# macropad.net
KiCad netlist of a schematic drawn in EAGLE
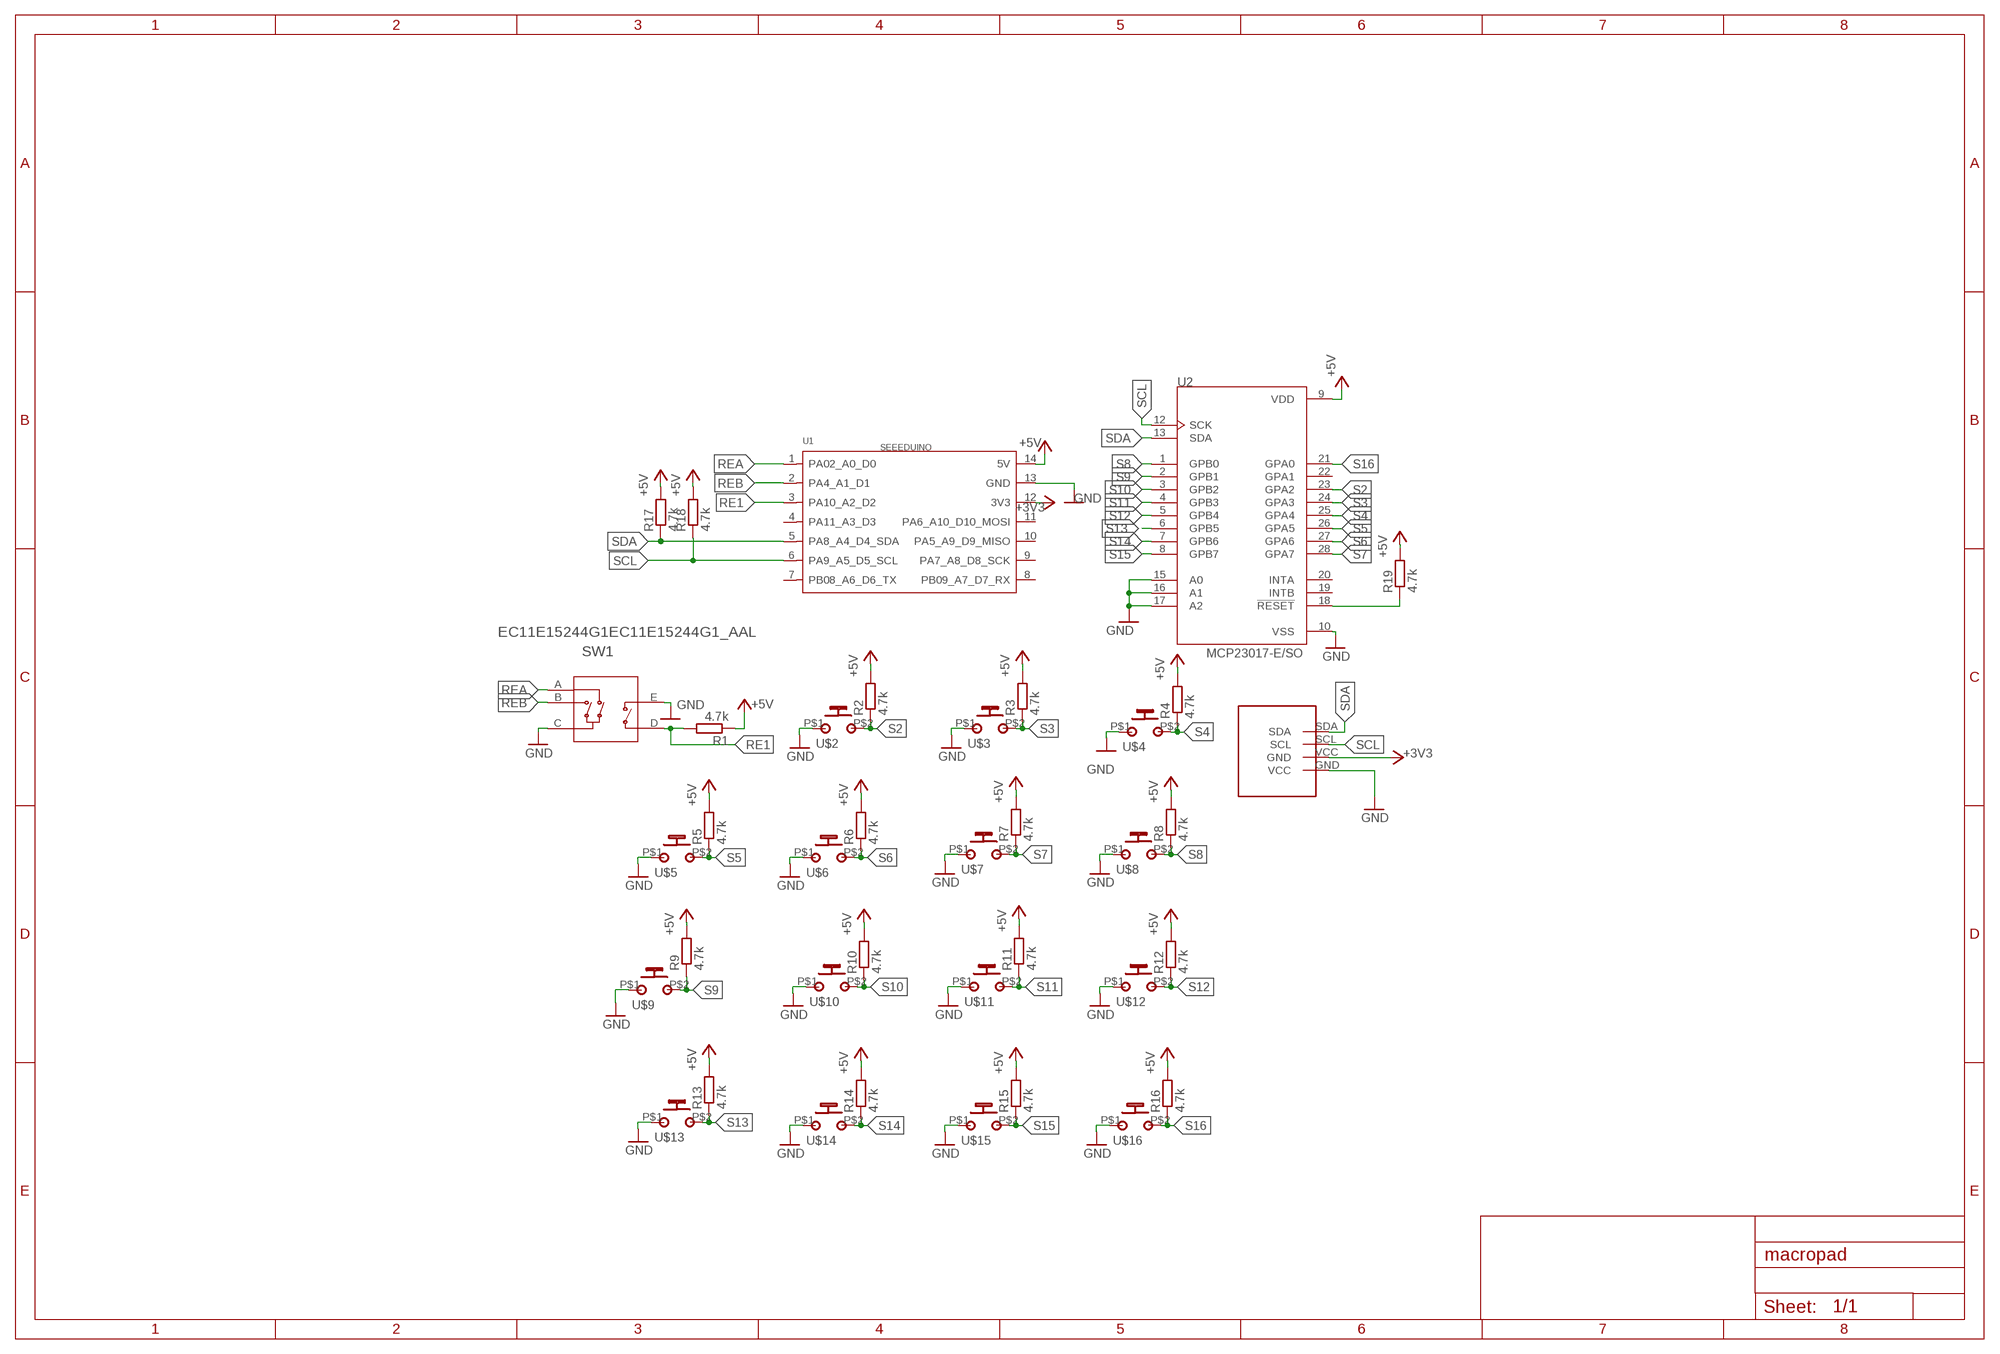
[diagram p0: schematic, sheet 1]

(export (version "E")
  (design (tool "Eeschema 10.0.6"))
  (components
    (comp (ref "DISPLAY")
      (value "OLED_0.96_I2C")
      (footprint "eagle-import:OLED_0.96_I2C")
      (libsource (lib "eagle-import") (part "OLED_0.96_I2C"))
    )
    (comp (ref "R1")
      (value "4.7k")
      (footprint "eagle-import:R0805")
      (libsource (lib "eagle-import") (part "R-EU_R0805"))
    )
    (comp (ref "R2")
      (value "4.7k")
      (footprint "eagle-import:R0805")
      (libsource (lib "eagle-import") (part "R-EU_R0805"))
    )
    (comp (ref "R3")
      (value "4.7k")
      (footprint "eagle-import:R0805")
      (libsource (lib "eagle-import") (part "R-EU_R0805"))
    )
    (comp (ref "R4")
      (value "4.7k")
      (footprint "eagle-import:R0805")
      (libsource (lib "eagle-import") (part "R-EU_R0805"))
    )
    (comp (ref "R5")
      (value "4.7k")
      (footprint "eagle-import:R0805")
      (libsource (lib "eagle-import") (part "R-EU_R0805"))
    )
    (comp (ref "R6")
      (value "4.7k")
      (footprint "eagle-import:R0805")
      (libsource (lib "eagle-import") (part "R-EU_R0805"))
    )
    (comp (ref "R7")
      (value "4.7k")
      (footprint "eagle-import:R0805")
      (libsource (lib "eagle-import") (part "R-EU_R0805"))
    )
    (comp (ref "R8")
      (value "4.7k")
      (footprint "eagle-import:R0805")
      (libsource (lib "eagle-import") (part "R-EU_R0805"))
    )
    (comp (ref "R9")
      (value "4.7k")
      (footprint "eagle-import:R0805")
      (libsource (lib "eagle-import") (part "R-EU_R0805"))
    )
    (comp (ref "R10")
      (value "4.7k")
      (footprint "eagle-import:R0805")
      (libsource (lib "eagle-import") (part "R-EU_R0805"))
    )
    (comp (ref "R11")
      (value "4.7k")
      (footprint "eagle-import:R0805")
      (libsource (lib "eagle-import") (part "R-EU_R0805"))
    )
    (comp (ref "R12")
      (value "4.7k")
      (footprint "eagle-import:R0805")
      (libsource (lib "eagle-import") (part "R-EU_R0805"))
    )
    (comp (ref "R13")
      (value "4.7k")
      (footprint "eagle-import:R0805")
      (libsource (lib "eagle-import") (part "R-EU_R0805"))
    )
    (comp (ref "R14")
      (value "4.7k")
      (footprint "eagle-import:R0805")
      (libsource (lib "eagle-import") (part "R-EU_R0805"))
    )
    (comp (ref "R15")
      (value "4.7k")
      (footprint "eagle-import:R0805")
      (libsource (lib "eagle-import") (part "R-EU_R0805"))
    )
    (comp (ref "R16")
      (value "4.7k")
      (footprint "eagle-import:R0805")
      (libsource (lib "eagle-import") (part "R-EU_R0805"))
    )
    (comp (ref "R17")
      (value "4.7k")
      (footprint "eagle-import:R0805")
      (libsource (lib "eagle-import") (part "R-EU_R0805"))
    )
    (comp (ref "R18")
      (value "4.7k")
      (footprint "eagle-import:R0805")
      (libsource (lib "eagle-import") (part "R-EU_R0805"))
    )
    (comp (ref "R19")
      (value "4.7k")
      (footprint "eagle-import:R0805")
      (libsource (lib "eagle-import") (part "R-EU_R0805"))
    )
    (comp (ref "SW1")
      (value "EC11E15244G1EC11E15244G1_AAL")
      (footprint "eagle-import:EC11E15244G1_AAL")
      (fields
        (field (name "MANUFACTURER_PART_NUMBER") "EC11E15244G1")
        (field (name "COPYRIGHT") "Copyright (C) 2023 Ultra Librarian. All rights reserved.")
      )
      (libsource (lib "eagle-import") (part "EC11E15244G1EC11E15244G1_AAL"))
    )
    (comp (ref "U$2")
      (value "MX1A-11NN")
      (footprint "eagle-import:CHERRY_MX1A-11NN_SWITCH")
      (fields (field (name "MF") "Cherry") (field (name "MP") "MX1A11NN"))
      (libsource (lib "eagle-import") (part "MX1A-11NN"))
    )
    (comp (ref "U$3")
      (value "MX1A-11NN")
      (footprint "eagle-import:CHERRY_MX1A-11NN_SWITCH")
      (fields (field (name "MF") "Cherry") (field (name "MP") "MX1A11NN"))
      (libsource (lib "eagle-import") (part "MX1A-11NN"))
    )
    (comp (ref "U$4")
      (value "MX1A-11NN")
      (footprint "eagle-import:CHERRY_MX1A-11NN_SWITCH")
      (fields (field (name "MF") "Cherry") (field (name "MP") "MX1A11NN"))
      (libsource (lib "eagle-import") (part "MX1A-11NN"))
    )
    (comp (ref "U$5")
      (value "MX1A-11NN")
      (footprint "eagle-import:CHERRY_MX1A-11NN_SWITCH")
      (fields (field (name "MF") "Cherry") (field (name "MP") "MX1A11NN"))
      (libsource (lib "eagle-import") (part "MX1A-11NN"))
    )
    (comp (ref "U$6")
      (value "MX1A-11NN")
      (footprint "eagle-import:CHERRY_MX1A-11NN_SWITCH")
      (fields (field (name "MF") "Cherry") (field (name "MP") "MX1A11NN"))
      (libsource (lib "eagle-import") (part "MX1A-11NN"))
    )
    (comp (ref "U$7")
      (value "MX1A-11NN")
      (footprint "eagle-import:CHERRY_MX1A-11NN_SWITCH")
      (fields (field (name "MF") "Cherry") (field (name "MP") "MX1A11NN"))
      (libsource (lib "eagle-import") (part "MX1A-11NN"))
    )
    (comp (ref "U$8")
      (value "MX1A-11NN")
      (footprint "eagle-import:CHERRY_MX1A-11NN_SWITCH")
      (fields (field (name "MF") "Cherry") (field (name "MP") "MX1A11NN"))
      (libsource (lib "eagle-import") (part "MX1A-11NN"))
    )
    (comp (ref "U$9")
      (value "MX1A-11NN")
      (footprint "eagle-import:CHERRY_MX1A-11NN_SWITCH")
      (fields (field (name "MF") "Cherry") (field (name "MP") "MX1A11NN"))
      (libsource (lib "eagle-import") (part "MX1A-11NN"))
    )
    (comp (ref "U$10")
      (value "MX1A-11NN")
      (footprint "eagle-import:CHERRY_MX1A-11NN_SWITCH")
      (fields (field (name "MF") "Cherry") (field (name "MP") "MX1A11NN"))
      (libsource (lib "eagle-import") (part "MX1A-11NN"))
    )
    (comp (ref "U$11")
      (value "MX1A-11NN")
      (footprint "eagle-import:CHERRY_MX1A-11NN_SWITCH")
      (fields (field (name "MF") "Cherry") (field (name "MP") "MX1A11NN"))
      (libsource (lib "eagle-import") (part "MX1A-11NN"))
    )
    (comp (ref "U$12")
      (value "MX1A-11NN")
      (footprint "eagle-import:CHERRY_MX1A-11NN_SWITCH")
      (fields (field (name "MF") "Cherry") (field (name "MP") "MX1A11NN"))
      (libsource (lib "eagle-import") (part "MX1A-11NN"))
    )
    (comp (ref "U$13")
      (value "MX1A-11NN")
      (footprint "eagle-import:CHERRY_MX1A-11NN_SWITCH")
      (fields (field (name "MF") "Cherry") (field (name "MP") "MX1A11NN"))
      (libsource (lib "eagle-import") (part "MX1A-11NN"))
    )
    (comp (ref "U$14")
      (value "MX1A-11NN")
      (footprint "eagle-import:CHERRY_MX1A-11NN_SWITCH")
      (fields (field (name "MF") "Cherry") (field (name "MP") "MX1A11NN"))
      (libsource (lib "eagle-import") (part "MX1A-11NN"))
    )
    (comp (ref "U$15")
      (value "MX1A-11NN")
      (footprint "eagle-import:CHERRY_MX1A-11NN_SWITCH")
      (fields (field (name "MF") "Cherry") (field (name "MP") "MX1A11NN"))
      (libsource (lib "eagle-import") (part "MX1A-11NN"))
    )
    (comp (ref "U$16")
      (value "MX1A-11NN")
      (footprint "eagle-import:CHERRY_MX1A-11NN_SWITCH")
      (fields (field (name "MF") "Cherry") (field (name "MP") "MX1A11NN"))
      (libsource (lib "eagle-import") (part "MX1A-11NN"))
    )
    (comp (ref "U1")
      (value "SEEEDUINO")
      (footprint "eagle-import:MOUDLE14P-2.54-21X17.8MM")
      (libsource (lib "eagle-import") (part "MOUDLE-SEEEDUINO-XIAO"))
    )
    (comp (ref "U2")
      (value "MCP23017-E/SO")
      (footprint "eagle-import:SOIC127P1030X265-28N")
      (fields (field (name "MF") "Microchip"))
      (libsource (lib "eagle-import") (part "MCP23017-E/SO"))
    )
  )
  (nets
    (net (code "1") (name "+3V3") (class "Default")
      (node (ref "DISPLAY") (pin "VCC") (pinfunction "GND_VCC") (pintype "bidirectional"))
      (node (ref "U1") (pin "12") (pinfunction "3V3_12") (pintype "bidirectional"))
    )
    (net (code "2") (name "+5V") (class "Default")
      (node (ref "R1") (pin "1") (pinfunction "1_1") (pintype "passive"))
      (node (ref "R10") (pin "2") (pinfunction "2_2") (pintype "passive"))
      (node (ref "R11") (pin "2") (pinfunction "2_2") (pintype "passive"))
      (node (ref "R12") (pin "2") (pinfunction "2_2") (pintype "passive"))
      (node (ref "R13") (pin "2") (pinfunction "2_2") (pintype "passive"))
      (node (ref "R14") (pin "2") (pinfunction "2_2") (pintype "passive"))
      (node (ref "R15") (pin "2") (pinfunction "2_2") (pintype "passive"))
      (node (ref "R16") (pin "2") (pinfunction "2_2") (pintype "passive"))
      (node (ref "R17") (pin "2") (pinfunction "2_2") (pintype "passive"))
      (node (ref "R18") (pin "2") (pinfunction "2_2") (pintype "passive"))
      (node (ref "R19") (pin "2") (pinfunction "2_2") (pintype "passive"))
      (node (ref "R2") (pin "2") (pinfunction "2_2") (pintype "passive"))
      (node (ref "R3") (pin "2") (pinfunction "2_2") (pintype "passive"))
      (node (ref "R4") (pin "2") (pinfunction "2_2") (pintype "passive"))
      (node (ref "R5") (pin "2") (pinfunction "2_2") (pintype "passive"))
      (node (ref "R6") (pin "2") (pinfunction "2_2") (pintype "passive"))
      (node (ref "R7") (pin "2") (pinfunction "2_2") (pintype "passive"))
      (node (ref "R8") (pin "2") (pinfunction "2_2") (pintype "passive"))
      (node (ref "R9") (pin "2") (pinfunction "2_2") (pintype "passive"))
      (node (ref "U1") (pin "14") (pinfunction "5V_14") (pintype "bidirectional"))
      (node (ref "U2") (pin "9") (pinfunction "VDD_9") (pintype "power_in"))
    )
    (net (code "3") (name "GND") (class "Default")
      (node (ref "DISPLAY") (pin "GND") (pinfunction "VCC_GND") (pintype "bidirectional"))
      (node (ref "SW1") (pin "C") (pinfunction "C_C") (pintype "passive"))
      (node (ref "SW1") (pin "E") (pinfunction "E_E") (pintype "passive"))
      (node (ref "U$10") (pin "P$1") (pinfunction "P_P$1") (pintype "passive"))
      (node (ref "U$11") (pin "P$1") (pinfunction "P_P$1") (pintype "passive"))
      (node (ref "U$12") (pin "P$1") (pinfunction "P_P$1") (pintype "passive"))
      (node (ref "U$13") (pin "P$1") (pinfunction "P_P$1") (pintype "passive"))
      (node (ref "U$14") (pin "P$1") (pinfunction "P_P$1") (pintype "passive"))
      (node (ref "U$15") (pin "P$1") (pinfunction "P_P$1") (pintype "passive"))
      (node (ref "U$16") (pin "P$1") (pinfunction "P_P$1") (pintype "passive"))
      (node (ref "U$2") (pin "P$1") (pinfunction "P_P$1") (pintype "passive"))
      (node (ref "U$3") (pin "P$1") (pinfunction "P_P$1") (pintype "passive"))
      (node (ref "U$4") (pin "P$1") (pinfunction "P_P$1") (pintype "passive"))
      (node (ref "U$5") (pin "P$1") (pinfunction "P_P$1") (pintype "passive"))
      (node (ref "U$6") (pin "P$1") (pinfunction "P_P$1") (pintype "passive"))
      (node (ref "U$7") (pin "P$1") (pinfunction "P_P$1") (pintype "passive"))
      (node (ref "U$8") (pin "P$1") (pinfunction "P_P$1") (pintype "passive"))
      (node (ref "U$9") (pin "P$1") (pinfunction "P_P$1") (pintype "passive"))
      (node (ref "U1") (pin "13") (pinfunction "GND_13") (pintype "bidirectional"))
      (node (ref "U2") (pin "10") (pinfunction "VSS_10") (pintype "power_in"))
      (node (ref "U2") (pin "15") (pinfunction "A0_15") (pintype "input"))
      (node (ref "U2") (pin "16") (pinfunction "A1_16") (pintype "input"))
      (node (ref "U2") (pin "17") (pinfunction "A2_17") (pintype "input"))
    )
    (net (code "4") (name "Net-(U2-~{RESET})") (class "Default")
      (node (ref "R19") (pin "1") (pinfunction "1_1") (pintype "passive"))
      (node (ref "U2") (pin "18") (pinfunction "~{RESET}_18") (pintype "output"))
    )
    (net (code "5") (name "RE1") (class "Default")
      (node (ref "R1") (pin "2") (pinfunction "2_2") (pintype "passive"))
      (node (ref "SW1") (pin "D") (pinfunction "D_D") (pintype "passive"))
      (node (ref "U1") (pin "3") (pinfunction "PA10_A2_D2_3") (pintype "bidirectional"))
    )
    (net (code "6") (name "REA") (class "Default")
      (node (ref "SW1") (pin "A") (pinfunction "A_A") (pintype "passive"))
      (node (ref "U1") (pin "1") (pinfunction "PA02_A0_D0_1") (pintype "bidirectional"))
    )
    (net (code "7") (name "REB") (class "Default")
      (node (ref "SW1") (pin "B") (pinfunction "B_B") (pintype "passive"))
      (node (ref "U1") (pin "2") (pinfunction "PA4_A1_D1_2") (pintype "bidirectional"))
    )
    (net (code "8") (name "S2") (class "Default")
      (node (ref "R2") (pin "1") (pinfunction "1_1") (pintype "passive"))
      (node (ref "U$2") (pin "P$2") (pinfunction "S_P$2") (pintype "passive"))
      (node (ref "U2") (pin "23") (pinfunction "GPA2_23") (pintype "bidirectional"))
    )
    (net (code "9") (name "S3") (class "Default")
      (node (ref "R3") (pin "1") (pinfunction "1_1") (pintype "passive"))
      (node (ref "U$3") (pin "P$2") (pinfunction "S_P$2") (pintype "passive"))
      (node (ref "U2") (pin "24") (pinfunction "GPA3_24") (pintype "bidirectional"))
    )
    (net (code "10") (name "S4") (class "Default")
      (node (ref "R4") (pin "1") (pinfunction "1_1") (pintype "passive"))
      (node (ref "U$4") (pin "P$2") (pinfunction "S_P$2") (pintype "passive"))
      (node (ref "U2") (pin "25") (pinfunction "GPA4_25") (pintype "bidirectional"))
    )
    (net (code "11") (name "S5") (class "Default")
      (node (ref "R5") (pin "1") (pinfunction "1_1") (pintype "passive"))
      (node (ref "U$5") (pin "P$2") (pinfunction "S_P$2") (pintype "passive"))
      (node (ref "U2") (pin "26") (pinfunction "GPA5_26") (pintype "bidirectional"))
    )
    (net (code "12") (name "S6") (class "Default")
      (node (ref "R6") (pin "1") (pinfunction "1_1") (pintype "passive"))
      (node (ref "U$6") (pin "P$2") (pinfunction "S_P$2") (pintype "passive"))
      (node (ref "U2") (pin "27") (pinfunction "GPA6_27") (pintype "bidirectional"))
    )
    (net (code "13") (name "S7") (class "Default")
      (node (ref "R7") (pin "1") (pinfunction "1_1") (pintype "passive"))
      (node (ref "U$7") (pin "P$2") (pinfunction "S_P$2") (pintype "passive"))
      (node (ref "U2") (pin "28") (pinfunction "GPA7_28") (pintype "bidirectional"))
    )
    (net (code "14") (name "S8") (class "Default")
      (node (ref "R8") (pin "1") (pinfunction "1_1") (pintype "passive"))
      (node (ref "U$8") (pin "P$2") (pinfunction "S_P$2") (pintype "passive"))
      (node (ref "U2") (pin "1") (pinfunction "GPB0_1") (pintype "bidirectional"))
    )
    (net (code "15") (name "S9") (class "Default")
      (node (ref "R9") (pin "1") (pinfunction "1_1") (pintype "passive"))
      (node (ref "U$9") (pin "P$2") (pinfunction "S_P$2") (pintype "passive"))
      (node (ref "U2") (pin "2") (pinfunction "GPB1_2") (pintype "bidirectional"))
    )
    (net (code "16") (name "S10") (class "Default")
      (node (ref "R10") (pin "1") (pinfunction "1_1") (pintype "passive"))
      (node (ref "U$10") (pin "P$2") (pinfunction "S_P$2") (pintype "passive"))
      (node (ref "U2") (pin "3") (pinfunction "GPB2_3") (pintype "bidirectional"))
    )
    (net (code "17") (name "S11") (class "Default")
      (node (ref "R11") (pin "1") (pinfunction "1_1") (pintype "passive"))
      (node (ref "U$11") (pin "P$2") (pinfunction "S_P$2") (pintype "passive"))
      (node (ref "U2") (pin "4") (pinfunction "GPB3_4") (pintype "bidirectional"))
    )
    (net (code "18") (name "S12") (class "Default")
      (node (ref "R12") (pin "1") (pinfunction "1_1") (pintype "passive"))
      (node (ref "U$12") (pin "P$2") (pinfunction "S_P$2") (pintype "passive"))
      (node (ref "U2") (pin "5") (pinfunction "GPB4_5") (pintype "bidirectional"))
    )
    (net (code "19") (name "S13") (class "Default")
      (node (ref "R13") (pin "1") (pinfunction "1_1") (pintype "passive"))
      (node (ref "U$13") (pin "P$2") (pinfunction "S_P$2") (pintype "passive"))
      (node (ref "U2") (pin "6") (pinfunction "GPB5_6") (pintype "bidirectional"))
    )
    (net (code "20") (name "S14") (class "Default")
      (node (ref "R14") (pin "1") (pinfunction "1_1") (pintype "passive"))
      (node (ref "U$14") (pin "P$2") (pinfunction "S_P$2") (pintype "passive"))
      (node (ref "U2") (pin "7") (pinfunction "GPB6_7") (pintype "bidirectional"))
    )
    (net (code "21") (name "S15") (class "Default")
      (node (ref "R15") (pin "1") (pinfunction "1_1") (pintype "passive"))
      (node (ref "U$15") (pin "P$2") (pinfunction "S_P$2") (pintype "passive"))
      (node (ref "U2") (pin "8") (pinfunction "GPB7_8") (pintype "bidirectional"))
    )
    (net (code "22") (name "S16") (class "Default")
      (node (ref "R16") (pin "1") (pinfunction "1_1") (pintype "passive"))
      (node (ref "U$16") (pin "P$2") (pinfunction "S_P$2") (pintype "passive"))
      (node (ref "U2") (pin "21") (pinfunction "GPA0_21") (pintype "bidirectional"))
    )
    (net (code "23") (name "SCL") (class "Default")
      (node (ref "DISPLAY") (pin "SCL") (pinfunction "SCL_SCL") (pintype "bidirectional"))
      (node (ref "R18") (pin "1") (pinfunction "1_1") (pintype "passive"))
      (node (ref "U1") (pin "6") (pinfunction "PA9_A5_D5_SCL_6") (pintype "bidirectional"))
      (node (ref "U2") (pin "12") (pinfunction "SCK_12") (pintype "input"))
    )
    (net (code "24") (name "SDA") (class "Default")
      (node (ref "DISPLAY") (pin "SDA") (pinfunction "SDA_SDA") (pintype "bidirectional"))
      (node (ref "R17") (pin "1") (pinfunction "1_1") (pintype "passive"))
      (node (ref "U1") (pin "5") (pinfunction "PA8_A4_D4_SDA_5") (pintype "bidirectional"))
      (node (ref "U2") (pin "13") (pinfunction "SDA_13") (pintype "bidirectional"))
    )
    (net (code "25") (name "unconnected-(U1-PA5_A9_D9_MISO-Pad10)") (class "Default")
      (node (ref "U1") (pin "10") (pinfunction "PA5_A9_D9_MISO_10") (pintype "bidirectional"))
    )
    (net (code "26") (name "unconnected-(U1-PA6_A10_D10_MOSI-Pad11)") (class "Default")
      (node (ref "U1") (pin "11") (pinfunction "PA6_A10_D10_MOSI_11") (pintype "bidirectional"))
    )
    (net (code "27") (name "unconnected-(U1-PA7_A8_D8_SCK-Pad9)") (class "Default")
      (node (ref "U1") (pin "9") (pinfunction "PA7_A8_D8_SCK_9") (pintype "bidirectional"))
    )
    (net (code "28") (name "unconnected-(U1-PA11_A3_D3-Pad4)") (class "Default")
      (node (ref "U1") (pin "4") (pinfunction "PA11_A3_D3_4") (pintype "bidirectional"))
    )
    (net (code "29") (name "unconnected-(U1-PB08_A6_D6_TX-Pad7)") (class "Default")
      (node (ref "U1") (pin "7") (pinfunction "PB08_A6_D6_TX_7") (pintype "bidirectional"))
    )
    (net (code "30") (name "unconnected-(U1-PB09_A7_D7_RX-Pad8)") (class "Default")
      (node (ref "U1") (pin "8") (pinfunction "PB09_A7_D7_RX_8") (pintype "bidirectional"))
    )
    (net (code "31") (name "unconnected-(U2-GPA1-Pad22)") (class "Default")
      (node (ref "U2") (pin "22") (pinfunction "GPA1_22") (pintype "bidirectional"))
    )
    (net (code "32") (name "unconnected-(U2-INTA-Pad20)") (class "Default")
      (node (ref "U2") (pin "20") (pinfunction "INTA_20") (pintype "output"))
    )
    (net (code "33") (name "unconnected-(U2-INTB-Pad19)") (class "Default")
      (node (ref "U2") (pin "19") (pinfunction "INTB_19") (pintype "output"))
    )
  )
)
